# 1GB_DDR3L_Modules.net
KiCad netlist of a schematic drawn in Altium Designer
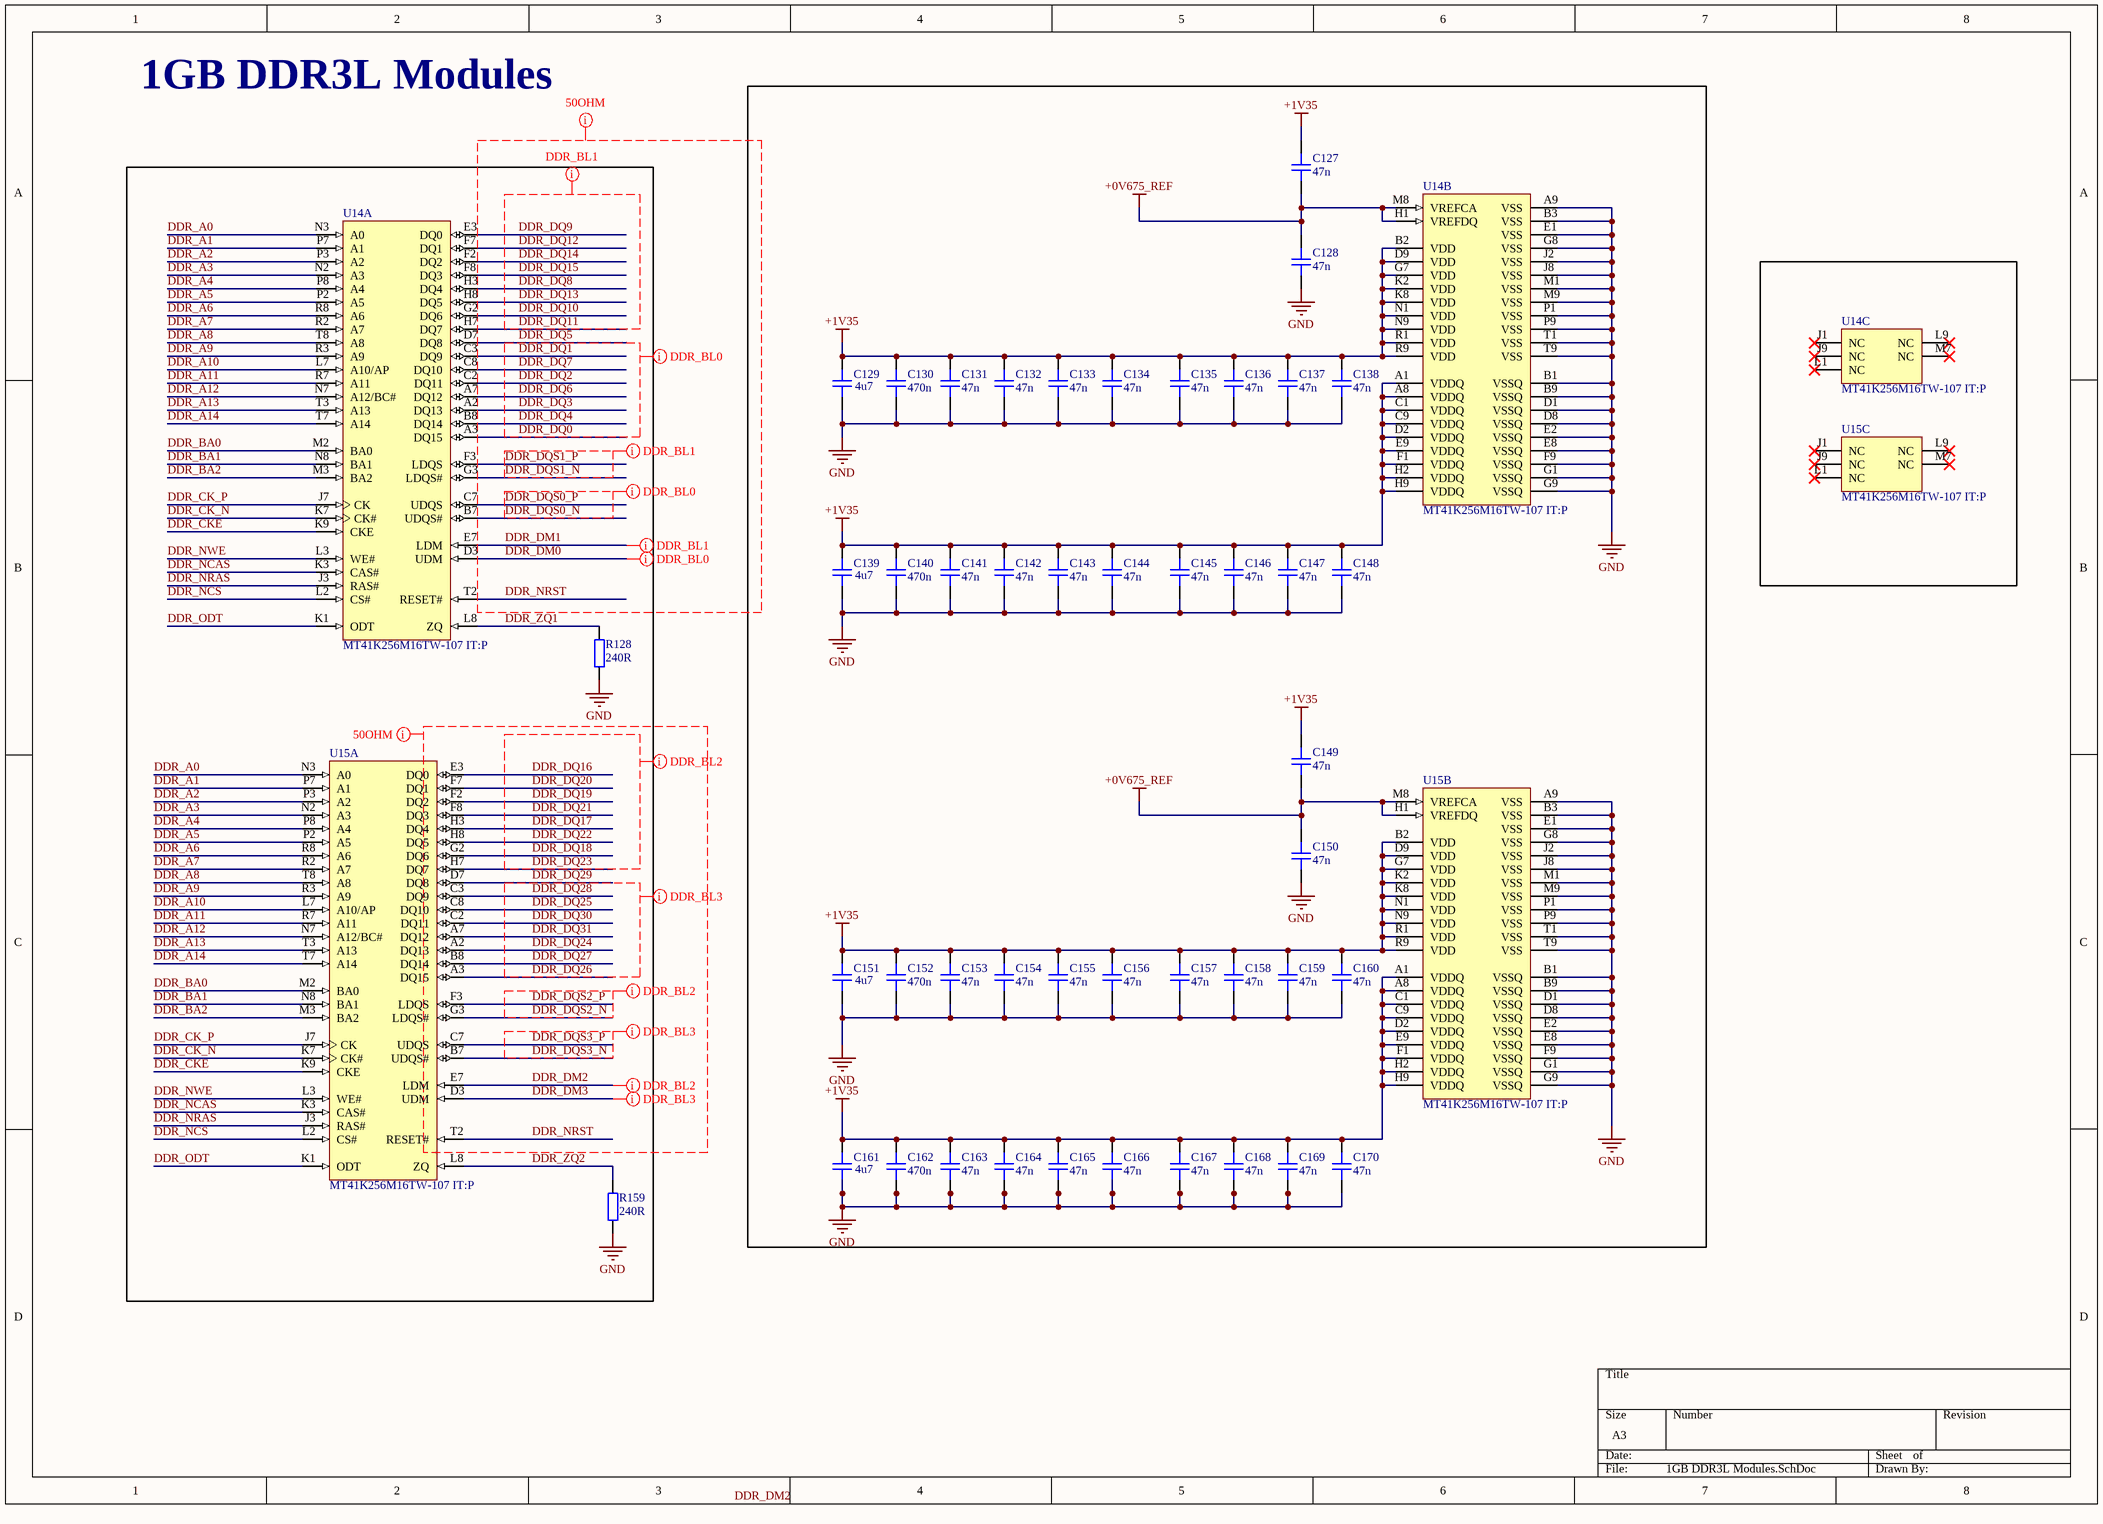
[diagram p0: 1GB DDR3L Modules.SchDoc]

(export (version "E")
  (design (tool "Eeschema 10.0.6"))
  (components
    (comp (ref "C127")
      (value "47n")
      (footprint "CAP_0201")
      (description "Capacitor SMD 0201")
      (fields (field (name "Comment") "C0201"))
      (libsource (lib "Schematic-Lib-PhilsLab") (part "CAP_0201"))
    )
    (comp (ref "C128")
      (value "47n")
      (footprint "CAP_0201")
      (description "Capacitor SMD 0201")
      (fields (field (name "Comment") "C0201"))
      (libsource (lib "Schematic-Lib-PhilsLab") (part "CAP_0201"))
    )
    (comp (ref "C129")
      (value "4u7")
      (footprint "CAP_0402")
      (description "Capacitor SMD 0402")
      (fields (field (name "Comment") "C0402"))
      (libsource (lib "Schematic-Lib-PhilsLab") (part "CAP_0402"))
    )
    (comp (ref "C130")
      (value "470n")
      (footprint "CAP_0201")
      (description "Capacitor SMD 0201")
      (fields (field (name "Comment") "C0201"))
      (libsource (lib "Schematic-Lib-PhilsLab") (part "CAP_0201"))
    )
    (comp (ref "C131")
      (value "47n")
      (footprint "CAP_0201")
      (description "Capacitor SMD 0201")
      (fields (field (name "Comment") "C0201"))
      (libsource (lib "Schematic-Lib-PhilsLab") (part "CAP_0201"))
    )
    (comp (ref "C132")
      (value "47n")
      (footprint "CAP_0201")
      (description "Capacitor SMD 0201")
      (fields (field (name "Comment") "C0201"))
      (libsource (lib "Schematic-Lib-PhilsLab") (part "CAP_0201"))
    )
    (comp (ref "C133")
      (value "47n")
      (footprint "CAP_0201")
      (description "Capacitor SMD 0201")
      (fields (field (name "Comment") "C0201"))
      (libsource (lib "Schematic-Lib-PhilsLab") (part "CAP_0201"))
    )
    (comp (ref "C134")
      (value "47n")
      (footprint "CAP_0201")
      (description "Capacitor SMD 0201")
      (fields (field (name "Comment") "C0201"))
      (libsource (lib "Schematic-Lib-PhilsLab") (part "CAP_0201"))
    )
    (comp (ref "C135")
      (value "47n")
      (footprint "CAP_0201")
      (description "Capacitor SMD 0201")
      (fields (field (name "Comment") "C0201"))
      (libsource (lib "Schematic-Lib-PhilsLab") (part "CAP_0201"))
    )
    (comp (ref "C136")
      (value "47n")
      (footprint "CAP_0201")
      (description "Capacitor SMD 0201")
      (fields (field (name "Comment") "C0201"))
      (libsource (lib "Schematic-Lib-PhilsLab") (part "CAP_0201"))
    )
    (comp (ref "C137")
      (value "47n")
      (footprint "CAP_0201")
      (description "Capacitor SMD 0201")
      (fields (field (name "Comment") "C0201"))
      (libsource (lib "Schematic-Lib-PhilsLab") (part "CAP_0201"))
    )
    (comp (ref "C138")
      (value "47n")
      (footprint "CAP_0201")
      (description "Capacitor SMD 0201")
      (fields (field (name "Comment") "C0201"))
      (libsource (lib "Schematic-Lib-PhilsLab") (part "CAP_0201"))
    )
    (comp (ref "C139")
      (value "4u7")
      (footprint "CAP_0402")
      (description "Capacitor SMD 0402")
      (fields (field (name "Comment") "C0402"))
      (libsource (lib "Schematic-Lib-PhilsLab") (part "CAP_0402"))
    )
    (comp (ref "C140")
      (value "470n")
      (footprint "CAP_0201")
      (description "Capacitor SMD 0201")
      (fields (field (name "Comment") "C0201"))
      (libsource (lib "Schematic-Lib-PhilsLab") (part "CAP_0201"))
    )
    (comp (ref "C141")
      (value "47n")
      (footprint "CAP_0201")
      (description "Capacitor SMD 0201")
      (fields (field (name "Comment") "C0201"))
      (libsource (lib "Schematic-Lib-PhilsLab") (part "CAP_0201"))
    )
    (comp (ref "C142")
      (value "47n")
      (footprint "CAP_0201")
      (description "Capacitor SMD 0201")
      (fields (field (name "Comment") "C0201"))
      (libsource (lib "Schematic-Lib-PhilsLab") (part "CAP_0201"))
    )
    (comp (ref "C143")
      (value "47n")
      (footprint "CAP_0201")
      (description "Capacitor SMD 0201")
      (fields (field (name "Comment") "C0201"))
      (libsource (lib "Schematic-Lib-PhilsLab") (part "CAP_0201"))
    )
    (comp (ref "C144")
      (value "47n")
      (footprint "CAP_0201")
      (description "Capacitor SMD 0201")
      (fields (field (name "Comment") "C0201"))
      (libsource (lib "Schematic-Lib-PhilsLab") (part "CAP_0201"))
    )
    (comp (ref "C145")
      (value "47n")
      (footprint "CAP_0201")
      (description "Capacitor SMD 0201")
      (fields (field (name "Comment") "C0201"))
      (libsource (lib "Schematic-Lib-PhilsLab") (part "CAP_0201"))
    )
    (comp (ref "C146")
      (value "47n")
      (footprint "CAP_0201")
      (description "Capacitor SMD 0201")
      (fields (field (name "Comment") "C0201"))
      (libsource (lib "Schematic-Lib-PhilsLab") (part "CAP_0201"))
    )
    (comp (ref "C147")
      (value "47n")
      (footprint "CAP_0201")
      (description "Capacitor SMD 0201")
      (fields (field (name "Comment") "C0201"))
      (libsource (lib "Schematic-Lib-PhilsLab") (part "CAP_0201"))
    )
    (comp (ref "C148")
      (value "47n")
      (footprint "CAP_0201")
      (description "Capacitor SMD 0201")
      (fields (field (name "Comment") "C0201"))
      (libsource (lib "Schematic-Lib-PhilsLab") (part "CAP_0201"))
    )
    (comp (ref "C149")
      (value "47n")
      (footprint "CAP_0201")
      (description "Capacitor SMD 0201")
      (fields (field (name "Comment") "C0201"))
      (libsource (lib "Schematic-Lib-PhilsLab") (part "CAP_0201"))
    )
    (comp (ref "C150")
      (value "47n")
      (footprint "CAP_0201")
      (description "Capacitor SMD 0201")
      (fields (field (name "Comment") "C0201"))
      (libsource (lib "Schematic-Lib-PhilsLab") (part "CAP_0201"))
    )
    (comp (ref "C151")
      (value "4u7")
      (footprint "CAP_0402")
      (description "Capacitor SMD 0402")
      (fields (field (name "Comment") "C0402"))
      (libsource (lib "Schematic-Lib-PhilsLab") (part "CAP_0402"))
    )
    (comp (ref "C152")
      (value "470n")
      (footprint "CAP_0201")
      (description "Capacitor SMD 0201")
      (fields (field (name "Comment") "C0201"))
      (libsource (lib "Schematic-Lib-PhilsLab") (part "CAP_0201"))
    )
    (comp (ref "C153")
      (value "47n")
      (footprint "CAP_0201")
      (description "Capacitor SMD 0201")
      (fields (field (name "Comment") "C0201"))
      (libsource (lib "Schematic-Lib-PhilsLab") (part "CAP_0201"))
    )
    (comp (ref "C154")
      (value "47n")
      (footprint "CAP_0201")
      (description "Capacitor SMD 0201")
      (fields (field (name "Comment") "C0201"))
      (libsource (lib "Schematic-Lib-PhilsLab") (part "CAP_0201"))
    )
    (comp (ref "C155")
      (value "47n")
      (footprint "CAP_0201")
      (description "Capacitor SMD 0201")
      (fields (field (name "Comment") "C0201"))
      (libsource (lib "Schematic-Lib-PhilsLab") (part "CAP_0201"))
    )
    (comp (ref "C156")
      (value "47n")
      (footprint "CAP_0201")
      (description "Capacitor SMD 0201")
      (fields (field (name "Comment") "C0201"))
      (libsource (lib "Schematic-Lib-PhilsLab") (part "CAP_0201"))
    )
    (comp (ref "C157")
      (value "47n")
      (footprint "CAP_0201")
      (description "Capacitor SMD 0201")
      (fields (field (name "Comment") "C0201"))
      (libsource (lib "Schematic-Lib-PhilsLab") (part "CAP_0201"))
    )
    (comp (ref "C158")
      (value "47n")
      (footprint "CAP_0201")
      (description "Capacitor SMD 0201")
      (fields (field (name "Comment") "C0201"))
      (libsource (lib "Schematic-Lib-PhilsLab") (part "CAP_0201"))
    )
    (comp (ref "C159")
      (value "47n")
      (footprint "CAP_0201")
      (description "Capacitor SMD 0201")
      (fields (field (name "Comment") "C0201"))
      (libsource (lib "Schematic-Lib-PhilsLab") (part "CAP_0201"))
    )
    (comp (ref "C160")
      (value "47n")
      (footprint "CAP_0201")
      (description "Capacitor SMD 0201")
      (fields (field (name "Comment") "C0201"))
      (libsource (lib "Schematic-Lib-PhilsLab") (part "CAP_0201"))
    )
    (comp (ref "C161")
      (value "4u7")
      (footprint "CAP_0402")
      (description "Capacitor SMD 0402")
      (fields (field (name "Comment") "C0402"))
      (libsource (lib "Schematic-Lib-PhilsLab") (part "CAP_0402"))
    )
    (comp (ref "C162")
      (value "470n")
      (footprint "CAP_0201")
      (description "Capacitor SMD 0201")
      (fields (field (name "Comment") "C0201"))
      (libsource (lib "Schematic-Lib-PhilsLab") (part "CAP_0201"))
    )
    (comp (ref "C163")
      (value "47n")
      (footprint "CAP_0201")
      (description "Capacitor SMD 0201")
      (fields (field (name "Comment") "C0201"))
      (libsource (lib "Schematic-Lib-PhilsLab") (part "CAP_0201"))
    )
    (comp (ref "C164")
      (value "47n")
      (footprint "CAP_0201")
      (description "Capacitor SMD 0201")
      (fields (field (name "Comment") "C0201"))
      (libsource (lib "Schematic-Lib-PhilsLab") (part "CAP_0201"))
    )
    (comp (ref "C165")
      (value "47n")
      (footprint "CAP_0201")
      (description "Capacitor SMD 0201")
      (fields (field (name "Comment") "C0201"))
      (libsource (lib "Schematic-Lib-PhilsLab") (part "CAP_0201"))
    )
    (comp (ref "C166")
      (value "47n")
      (footprint "CAP_0201")
      (description "Capacitor SMD 0201")
      (fields (field (name "Comment") "C0201"))
      (libsource (lib "Schematic-Lib-PhilsLab") (part "CAP_0201"))
    )
    (comp (ref "C167")
      (value "47n")
      (footprint "CAP_0201")
      (description "Capacitor SMD 0201")
      (fields (field (name "Comment") "C0201"))
      (libsource (lib "Schematic-Lib-PhilsLab") (part "CAP_0201"))
    )
    (comp (ref "C168")
      (value "47n")
      (footprint "CAP_0201")
      (description "Capacitor SMD 0201")
      (fields (field (name "Comment") "C0201"))
      (libsource (lib "Schematic-Lib-PhilsLab") (part "CAP_0201"))
    )
    (comp (ref "C169")
      (value "47n")
      (footprint "CAP_0201")
      (description "Capacitor SMD 0201")
      (fields (field (name "Comment") "C0201"))
      (libsource (lib "Schematic-Lib-PhilsLab") (part "CAP_0201"))
    )
    (comp (ref "C170")
      (value "47n")
      (footprint "CAP_0201")
      (description "Capacitor SMD 0201")
      (fields (field (name "Comment") "C0201"))
      (libsource (lib "Schematic-Lib-PhilsLab") (part "CAP_0201"))
    )
    (comp (ref "R128")
      (value "240R")
      (footprint "RES_0402")
      (description "Resistor SMD 0402")
      (fields (field (name "Comment") "R0402"))
      (libsource (lib "Schematic-Lib-PhilsLab") (part "RES_0402"))
    )
    (comp (ref "R159")
      (value "240R")
      (footprint "RES_0402")
      (description "Resistor SMD 0402")
      (fields (field (name "Comment") "R0402"))
      (libsource (lib "Schematic-Lib-PhilsLab") (part "RES_0402"))
    )
    (comp (ref "U14")
      (value "MT41K256M16TW-107 IT:P")
      (footprint "MICT-TW-96")
      (description "Automotive DDR3L SDRAM, 4 GB, 933 MHz, 1.283 to 1.45 V, -40 to 95 degC, 96-Pin TFBGA, RoHS, Tray")
      (fields (field (name "MANUFACTURER") "Micron"))
      (libsource (lib "Altium Content Vault") (part "MICT-MT41K256M16-TW-96"))
    )
    (comp (ref "U15")
      (value "MT41K256M16TW-107 IT:P")
      (footprint "MICT-TW-96")
      (description "Automotive DDR3L SDRAM, 4 GB, 933 MHz, 1.283 to 1.45 V, -40 to 95 degC, 96-Pin TFBGA, RoHS, Tray")
      (fields (field (name "MANUFACTURER") "Micron"))
      (libsource (lib "Altium Content Vault") (part "MICT-MT41K256M16-TW-96"))
    )
  )
  (nets
    (net (code "1") (name "+0V675_REF") (class "Default")
      (node (ref "C127") (pin "1") (pinfunction "1_1") (pintype "passive"))
      (node (ref "C128") (pin "2") (pinfunction "2_2") (pintype "passive"))
      (node (ref "C149") (pin "1") (pinfunction "1_1") (pintype "passive"))
      (node (ref "C150") (pin "2") (pinfunction "2_2") (pintype "passive"))
      (node (ref "U14") (pin "H1") (pinfunction "VREFDQ_H1") (pintype "input"))
      (node (ref "U14") (pin "M8") (pinfunction "VREFCA_M8") (pintype "input"))
      (node (ref "U15") (pin "H1") (pinfunction "VREFDQ_H1") (pintype "input"))
      (node (ref "U15") (pin "M8") (pinfunction "VREFCA_M8") (pintype "input"))
    )
    (net (code "2") (name "+1V35") (class "Default")
      (node (ref "C127") (pin "2") (pinfunction "2_2") (pintype "passive"))
      (node (ref "C129") (pin "2") (pinfunction "2_2") (pintype "passive"))
      (node (ref "C130") (pin "2") (pinfunction "2_2") (pintype "passive"))
      (node (ref "C131") (pin "2") (pinfunction "2_2") (pintype "passive"))
      (node (ref "C132") (pin "2") (pinfunction "2_2") (pintype "passive"))
      (node (ref "C133") (pin "2") (pinfunction "2_2") (pintype "passive"))
      (node (ref "C134") (pin "2") (pinfunction "2_2") (pintype "passive"))
      (node (ref "C135") (pin "2") (pinfunction "2_2") (pintype "passive"))
      (node (ref "C136") (pin "2") (pinfunction "2_2") (pintype "passive"))
      (node (ref "C137") (pin "2") (pinfunction "2_2") (pintype "passive"))
      (node (ref "C138") (pin "2") (pinfunction "2_2") (pintype "passive"))
      (node (ref "C139") (pin "2") (pinfunction "2_2") (pintype "passive"))
      (node (ref "C140") (pin "2") (pinfunction "2_2") (pintype "passive"))
      (node (ref "C141") (pin "2") (pinfunction "2_2") (pintype "passive"))
      (node (ref "C142") (pin "2") (pinfunction "2_2") (pintype "passive"))
      (node (ref "C143") (pin "2") (pinfunction "2_2") (pintype "passive"))
      (node (ref "C144") (pin "2") (pinfunction "2_2") (pintype "passive"))
      (node (ref "C145") (pin "2") (pinfunction "2_2") (pintype "passive"))
      (node (ref "C146") (pin "2") (pinfunction "2_2") (pintype "passive"))
      (node (ref "C147") (pin "2") (pinfunction "2_2") (pintype "passive"))
      (node (ref "C148") (pin "2") (pinfunction "2_2") (pintype "passive"))
      (node (ref "C149") (pin "2") (pinfunction "2_2") (pintype "passive"))
      (node (ref "C151") (pin "2") (pinfunction "2_2") (pintype "passive"))
      (node (ref "C152") (pin "2") (pinfunction "2_2") (pintype "passive"))
      (node (ref "C153") (pin "2") (pinfunction "2_2") (pintype "passive"))
      (node (ref "C154") (pin "2") (pinfunction "2_2") (pintype "passive"))
      (node (ref "C155") (pin "2") (pinfunction "2_2") (pintype "passive"))
      (node (ref "C156") (pin "2") (pinfunction "2_2") (pintype "passive"))
      (node (ref "C157") (pin "2") (pinfunction "2_2") (pintype "passive"))
      (node (ref "C158") (pin "2") (pinfunction "2_2") (pintype "passive"))
      (node (ref "C159") (pin "2") (pinfunction "2_2") (pintype "passive"))
      (node (ref "C160") (pin "2") (pinfunction "2_2") (pintype "passive"))
      (node (ref "C161") (pin "2") (pinfunction "2_2") (pintype "passive"))
      (node (ref "C162") (pin "2") (pinfunction "2_2") (pintype "passive"))
      (node (ref "C163") (pin "2") (pinfunction "2_2") (pintype "passive"))
      (node (ref "C164") (pin "2") (pinfunction "2_2") (pintype "passive"))
      (node (ref "C165") (pin "2") (pinfunction "2_2") (pintype "passive"))
      (node (ref "C166") (pin "2") (pinfunction "2_2") (pintype "passive"))
      (node (ref "C167") (pin "2") (pinfunction "2_2") (pintype "passive"))
      (node (ref "C168") (pin "2") (pinfunction "2_2") (pintype "passive"))
      (node (ref "C169") (pin "2") (pinfunction "2_2") (pintype "passive"))
      (node (ref "C170") (pin "2") (pinfunction "2_2") (pintype "passive"))
      (node (ref "U14") (pin "A1") (pinfunction "VDDQ_A1") (pintype "power_in"))
      (node (ref "U14") (pin "A8") (pinfunction "VDDQ_A8") (pintype "power_in"))
      (node (ref "U14") (pin "B2") (pinfunction "VDD_B2") (pintype "power_in"))
      (node (ref "U14") (pin "C1") (pinfunction "VDDQ_C1") (pintype "power_in"))
      (node (ref "U14") (pin "C9") (pinfunction "VDDQ_C9") (pintype "power_in"))
      (node (ref "U14") (pin "D2") (pinfunction "VDDQ_D2") (pintype "power_in"))
      (node (ref "U14") (pin "D9") (pinfunction "VDD_D9") (pintype "power_in"))
      (node (ref "U14") (pin "E9") (pinfunction "VDDQ_E9") (pintype "power_in"))
      (node (ref "U14") (pin "F1") (pinfunction "VDDQ_F1") (pintype "power_in"))
      (node (ref "U14") (pin "G7") (pinfunction "VDD_G7") (pintype "power_in"))
      (node (ref "U14") (pin "H2") (pinfunction "VDDQ_H2") (pintype "power_in"))
      (node (ref "U14") (pin "H9") (pinfunction "VDDQ_H9") (pintype "power_in"))
      (node (ref "U14") (pin "K2") (pinfunction "VDD_K2") (pintype "power_in"))
      (node (ref "U14") (pin "K8") (pinfunction "VDD_K8") (pintype "power_in"))
      (node (ref "U14") (pin "N1") (pinfunction "VDD_N1") (pintype "power_in"))
      (node (ref "U14") (pin "N9") (pinfunction "VDD_N9") (pintype "power_in"))
      (node (ref "U14") (pin "R1") (pinfunction "VDD_R1") (pintype "power_in"))
      (node (ref "U14") (pin "R9") (pinfunction "VDD_R9") (pintype "power_in"))
      (node (ref "U15") (pin "A1") (pinfunction "VDDQ_A1") (pintype "power_in"))
      (node (ref "U15") (pin "A8") (pinfunction "VDDQ_A8") (pintype "power_in"))
      (node (ref "U15") (pin "B2") (pinfunction "VDD_B2") (pintype "power_in"))
      (node (ref "U15") (pin "C1") (pinfunction "VDDQ_C1") (pintype "power_in"))
      (node (ref "U15") (pin "C9") (pinfunction "VDDQ_C9") (pintype "power_in"))
      (node (ref "U15") (pin "D2") (pinfunction "VDDQ_D2") (pintype "power_in"))
      (node (ref "U15") (pin "D9") (pinfunction "VDD_D9") (pintype "power_in"))
      (node (ref "U15") (pin "E9") (pinfunction "VDDQ_E9") (pintype "power_in"))
      (node (ref "U15") (pin "F1") (pinfunction "VDDQ_F1") (pintype "power_in"))
      (node (ref "U15") (pin "G7") (pinfunction "VDD_G7") (pintype "power_in"))
      (node (ref "U15") (pin "H2") (pinfunction "VDDQ_H2") (pintype "power_in"))
      (node (ref "U15") (pin "H9") (pinfunction "VDDQ_H9") (pintype "power_in"))
      (node (ref "U15") (pin "K2") (pinfunction "VDD_K2") (pintype "power_in"))
      (node (ref "U15") (pin "K8") (pinfunction "VDD_K8") (pintype "power_in"))
      (node (ref "U15") (pin "N1") (pinfunction "VDD_N1") (pintype "power_in"))
      (node (ref "U15") (pin "N9") (pinfunction "VDD_N9") (pintype "power_in"))
      (node (ref "U15") (pin "R1") (pinfunction "VDD_R1") (pintype "power_in"))
      (node (ref "U15") (pin "R9") (pinfunction "VDD_R9") (pintype "power_in"))
    )
    (net (code "3") (name "/DDR_A0") (class "Default")
      (node (ref "U14") (pin "N3") (pinfunction "A0_N3") (pintype "input"))
      (node (ref "U15") (pin "N3") (pinfunction "A0_N3") (pintype "input"))
    )
    (net (code "4") (name "/DDR_A1") (class "Default")
      (node (ref "U14") (pin "P7") (pinfunction "A1_P7") (pintype "input"))
      (node (ref "U15") (pin "P7") (pinfunction "A1_P7") (pintype "input"))
    )
    (net (code "5") (name "/DDR_A2") (class "Default")
      (node (ref "U14") (pin "P3") (pinfunction "A2_P3") (pintype "input"))
      (node (ref "U15") (pin "P3") (pinfunction "A2_P3") (pintype "input"))
    )
    (net (code "6") (name "/DDR_A3") (class "Default")
      (node (ref "U14") (pin "N2") (pinfunction "A3_N2") (pintype "input"))
      (node (ref "U15") (pin "N2") (pinfunction "A3_N2") (pintype "input"))
    )
    (net (code "7") (name "/DDR_A4") (class "Default")
      (node (ref "U14") (pin "P8") (pinfunction "A4_P8") (pintype "input"))
      (node (ref "U15") (pin "P8") (pinfunction "A4_P8") (pintype "input"))
    )
    (net (code "8") (name "/DDR_A5") (class "Default")
      (node (ref "U14") (pin "P2") (pinfunction "A5_P2") (pintype "input"))
      (node (ref "U15") (pin "P2") (pinfunction "A5_P2") (pintype "input"))
    )
    (net (code "9") (name "/DDR_A6") (class "Default")
      (node (ref "U14") (pin "R8") (pinfunction "A6_R8") (pintype "input"))
      (node (ref "U15") (pin "R8") (pinfunction "A6_R8") (pintype "input"))
    )
    (net (code "10") (name "/DDR_A7") (class "Default")
      (node (ref "U14") (pin "R2") (pinfunction "A7_R2") (pintype "input"))
      (node (ref "U15") (pin "R2") (pinfunction "A7_R2") (pintype "input"))
    )
    (net (code "11") (name "/DDR_A8") (class "Default")
      (node (ref "U14") (pin "T8") (pinfunction "A8_T8") (pintype "input"))
      (node (ref "U15") (pin "T8") (pinfunction "A8_T8") (pintype "input"))
    )
    (net (code "12") (name "/DDR_A9") (class "Default")
      (node (ref "U14") (pin "R3") (pinfunction "A9_R3") (pintype "input"))
      (node (ref "U15") (pin "R3") (pinfunction "A9_R3") (pintype "input"))
    )
    (net (code "13") (name "/DDR_A10") (class "Default")
      (node (ref "U14") (pin "L7") (pinfunction "A10/AP_L7") (pintype "input"))
      (node (ref "U15") (pin "L7") (pinfunction "A10/AP_L7") (pintype "input"))
    )
    (net (code "14") (name "/DDR_A11") (class "Default")
      (node (ref "U14") (pin "R7") (pinfunction "A11_R7") (pintype "input"))
      (node (ref "U15") (pin "R7") (pinfunction "A11_R7") (pintype "input"))
    )
    (net (code "15") (name "/DDR_A12") (class "Default")
      (node (ref "U14") (pin "N7") (pinfunction "A12/BC#_N7") (pintype "input"))
      (node (ref "U15") (pin "N7") (pinfunction "A12/BC#_N7") (pintype "input"))
    )
    (net (code "16") (name "/DDR_A13") (class "Default")
      (node (ref "U14") (pin "T3") (pinfunction "A13_T3") (pintype "input"))
      (node (ref "U15") (pin "T3") (pinfunction "A13_T3") (pintype "input"))
    )
    (net (code "17") (name "/DDR_A14") (class "Default")
      (node (ref "U14") (pin "T7") (pinfunction "A14_T7") (pintype "input"))
      (node (ref "U15") (pin "T7") (pinfunction "A14_T7") (pintype "input"))
    )
    (net (code "18") (name "/DDR_BA0") (class "Default")
      (node (ref "U14") (pin "M2") (pinfunction "BA0_M2") (pintype "input"))
      (node (ref "U15") (pin "M2") (pinfunction "BA0_M2") (pintype "input"))
    )
    (net (code "19") (name "/DDR_BA1") (class "Default")
      (node (ref "U14") (pin "N8") (pinfunction "BA1_N8") (pintype "input"))
      (node (ref "U15") (pin "N8") (pinfunction "BA1_N8") (pintype "input"))
    )
    (net (code "20") (name "/DDR_BA2") (class "Default")
      (node (ref "U14") (pin "M3") (pinfunction "BA2_M3") (pintype "input"))
      (node (ref "U15") (pin "M3") (pinfunction "BA2_M3") (pintype "input"))
    )
    (net (code "21") (name "/DDR_CKE") (class "Default")
      (node (ref "U14") (pin "K9") (pinfunction "CKE_K9") (pintype "input"))
      (node (ref "U15") (pin "K9") (pinfunction "CKE_K9") (pintype "input"))
    )
    (net (code "22") (name "/DDR_CK_N") (class "Default")
      (node (ref "U14") (pin "K7") (pinfunction "CK#_K7") (pintype "input"))
      (node (ref "U15") (pin "K7") (pinfunction "CK#_K7") (pintype "input"))
    )
    (net (code "23") (name "/DDR_CK_P") (class "Default")
      (node (ref "U14") (pin "J7") (pinfunction "CK_J7") (pintype "input"))
      (node (ref "U15") (pin "J7") (pinfunction "CK_J7") (pintype "input"))
    )
    (net (code "24") (name "/DDR_DM0") (class "Default")
      (node (ref "U14") (pin "D3") (pinfunction "UDM_D3") (pintype "input"))
    )
    (net (code "25") (name "/DDR_DM1") (class "Default")
      (node (ref "U14") (pin "E7") (pinfunction "LDM_E7") (pintype "input"))
    )
    (net (code "26") (name "/DDR_DM2") (class "Default")
      (node (ref "U15") (pin "E7") (pinfunction "LDM_E7") (pintype "input"))
    )
    (net (code "27") (name "/DDR_DM3") (class "Default")
      (node (ref "U15") (pin "D3") (pinfunction "UDM_D3") (pintype "input"))
    )
    (net (code "28") (name "/DDR_DQ0") (class "Default")
      (node (ref "U14") (pin "A3") (pinfunction "DQ15_A3") (pintype "bidirectional"))
    )
    (net (code "29") (name "/DDR_DQ1") (class "Default")
      (node (ref "U14") (pin "C3") (pinfunction "DQ9_C3") (pintype "bidirectional"))
    )
    (net (code "30") (name "/DDR_DQ2") (class "Default")
      (node (ref "U14") (pin "C2") (pinfunction "DQ11_C2") (pintype "bidirectional"))
    )
    (net (code "31") (name "/DDR_DQ3") (class "Default")
      (node (ref "U14") (pin "A2") (pinfunction "DQ13_A2") (pintype "bidirectional"))
    )
    (net (code "32") (name "/DDR_DQ4") (class "Default")
      (node (ref "U14") (pin "B8") (pinfunction "DQ14_B8") (pintype "bidirectional"))
    )
    (net (code "33") (name "/DDR_DQ5") (class "Default")
      (node (ref "U14") (pin "D7") (pinfunction "DQ8_D7") (pintype "bidirectional"))
    )
    (net (code "34") (name "/DDR_DQ6") (class "Default")
      (node (ref "U14") (pin "A7") (pinfunction "DQ12_A7") (pintype "bidirectional"))
    )
    (net (code "35") (name "/DDR_DQ7") (class "Default")
      (node (ref "U14") (pin "C8") (pinfunction "DQ10_C8") (pintype "bidirectional"))
    )
    (net (code "36") (name "/DDR_DQ8") (class "Default")
      (node (ref "U14") (pin "H3") (pinfunction "DQ4_H3") (pintype "bidirectional"))
    )
    (net (code "37") (name "/DDR_DQ9") (class "Default")
      (node (ref "U14") (pin "E3") (pinfunction "DQ0_E3") (pintype "bidirectional"))
    )
    (net (code "38") (name "/DDR_DQ10") (class "Default")
      (node (ref "U14") (pin "G2") (pinfunction "DQ6_G2") (pintype "bidirectional"))
    )
    (net (code "39") (name "/DDR_DQ11") (class "Default")
      (node (ref "U14") (pin "H7") (pinfunction "DQ7_H7") (pintype "bidirectional"))
    )
    (net (code "40") (name "/DDR_DQ12") (class "Default")
      (node (ref "U14") (pin "F7") (pinfunction "DQ1_F7") (pintype "bidirectional"))
    )
    (net (code "41") (name "/DDR_DQ13") (class "Default")
      (node (ref "U14") (pin "H8") (pinfunction "DQ5_H8") (pintype "bidirectional"))
    )
    (net (code "42") (name "/DDR_DQ14") (class "Default")
      (node (ref "U14") (pin "F2") (pinfunction "DQ2_F2") (pintype "bidirectional"))
    )
    (net (code "43") (name "/DDR_DQ15") (class "Default")
      (node (ref "U14") (pin "F8") (pinfunction "DQ3_F8") (pintype "bidirectional"))
    )
    (net (code "44") (name "/DDR_DQ16") (class "Default")
      (node (ref "U15") (pin "E3") (pinfunction "DQ0_E3") (pintype "bidirectional"))
    )
    (net (code "45") (name "/DDR_DQ17") (class "Default")
      (node (ref "U15") (pin "H3") (pinfunction "DQ4_H3") (pintype "bidirectional"))
    )
    (net (code "46") (name "/DDR_DQ18") (class "Default")
      (node (ref "U15") (pin "G2") (pinfunction "DQ6_G2") (pintype "bidirectional"))
    )
    (net (code "47") (name "/DDR_DQ19") (class "Default")
      (node (ref "U15") (pin "F2") (pinfunction "DQ2_F2") (pintype "bidirectional"))
    )
    (net (code "48") (name "/DDR_DQ20") (class "Default")
      (node (ref "U15") (pin "F7") (pinfunction "DQ1_F7") (pintype "bidirectional"))
    )
    (net (code "49") (name "/DDR_DQ21") (class "Default")
      (node (ref "U15") (pin "F8") (pinfunction "DQ3_F8") (pintype "bidirectional"))
    )
    (net (code "50") (name "/DDR_DQ22") (class "Default")
      (node (ref "U15") (pin "H8") (pinfunction "DQ5_H8") (pintype "bidirectional"))
    )
    (net (code "51") (name "/DDR_DQ23") (class "Default")
      (node (ref "U15") (pin "H7") (pinfunction "DQ7_H7") (pintype "bidirectional"))
    )
    (net (code "52") (name "/DDR_DQ24") (class "Default")
      (node (ref "U15") (pin "A2") (pinfunction "DQ13_A2") (pintype "bidirectional"))
    )
    (net (code "53") (name "/DDR_DQ25") (class "Default")
      (node (ref "U15") (pin "C8") (pinfunction "DQ10_C8") (pintype "bidirectional"))
    )
    (net (code "54") (name "/DDR_DQ26") (class "Default")
      (node (ref "U15") (pin "A3") (pinfunction "DQ15_A3") (pintype "bidirectional"))
    )
    (net (code "55") (name "/DDR_DQ27") (class "Default")
      (node (ref "U15") (pin "B8") (pinfunction "DQ14_B8") (pintype "bidirectional"))
    )
    (net (code "56") (name "/DDR_DQ28") (class "Default")
      (node (ref "U15") (pin "C3") (pinfunction "DQ9_C3") (pintype "bidirectional"))
    )
    (net (code "57") (name "/DDR_DQ29") (class "Default")
      (node (ref "U15") (pin "D7") (pinfunction "DQ8_D7") (pintype "bidirectional"))
    )
    (net (code "58") (name "/DDR_DQ30") (class "Default")
      (node (ref "U15") (pin "C2") (pinfunction "DQ11_C2") (pintype "bidirectional"))
    )
    (net (code "59") (name "/DDR_DQ31") (class "Default")
      (node (ref "U15") (pin "A7") (pinfunction "DQ12_A7") (pintype "bidirectional"))
    )
    (net (code "60") (name "/DDR_DQS0_N") (class "Default")
      (node (ref "U14") (pin "B7") (pinfunction "UDQS#_B7") (pintype "bidirectional"))
    )
    (net (code "61") (name "/DDR_DQS0_P") (class "Default")
      (node (ref "U14") (pin "C7") (pinfunction "UDQS_C7") (pintype "bidirectional"))
    )
    (net (code "62") (name "/DDR_DQS1_N") (class "Default")
      (node (ref "U14") (pin "G3") (pinfunction "LDQS#_G3") (pintype "bidirectional"))
    )
    (net (code "63") (name "/DDR_DQS1_P") (class "Default")
      (node (ref "U14") (pin "F3") (pinfunction "LDQS_F3") (pintype "bidirectional"))
    )
    (net (code "64") (name "/DDR_DQS2_N") (class "Default")
      (node (ref "U15") (pin "G3") (pinfunction "LDQS#_G3") (pintype "bidirectional"))
    )
    (net (code "65") (name "/DDR_DQS2_P") (class "Default")
      (node (ref "U15") (pin "F3") (pinfunction "LDQS_F3") (pintype "bidirectional"))
    )
    (net (code "66") (name "/DDR_DQS3_N") (class "Default")
      (node (ref "U15") (pin "B7") (pinfunction "UDQS#_B7") (pintype "bidirectional"))
    )
    (net (code "67") (name "/DDR_DQS3_P") (class "Default")
      (node (ref "U15") (pin "C7") (pinfunction "UDQS_C7") (pintype "bidirectional"))
    )
    (net (code "68") (name "/DDR_NCAS") (class "Default")
      (node (ref "U14") (pin "K3") (pinfunction "CAS#_K3") (pintype "input"))
      (node (ref "U15") (pin "K3") (pinfunction "CAS#_K3") (pintype "input"))
    )
    (net (code "69") (name "/DDR_NCS") (class "Default")
      (node (ref "U14") (pin "L2") (pinfunction "CS#_L2") (pintype "input"))
      (node (ref "U15") (pin "L2") (pinfunction "CS#_L2") (pintype "input"))
    )
    (net (code "70") (name "/DDR_NRAS") (class "Default")
      (node (ref "U14") (pin "J3") (pinfunction "RAS#_J3") (pintype "input"))
      (node (ref "U15") (pin "J3") (pinfunction "RAS#_J3") (pintype "input"))
    )
    (net (code "71") (name "/DDR_NRST") (class "Default")
      (node (ref "U14") (pin "T2") (pinfunction "RESET#_T2") (pintype "input"))
      (node (ref "U15") (pin "T2") (pinfunction "RESET#_T2") (pintype "input"))
    )
    (net (code "72") (name "/DDR_NWE") (class "Default")
      (node (ref "U14") (pin "L3") (pinfunction "WE#_L3") (pintype "input"))
      (node (ref "U15") (pin "L3") (pinfunction "WE#_L3") (pintype "input"))
    )
    (net (code "73") (name "/DDR_ODT") (class "Default")
      (node (ref "U14") (pin "K1") (pinfunction "ODT_K1") (pintype "input"))
      (node (ref "U15") (pin "K1") (pinfunction "ODT_K1") (pintype "input"))
    )
    (net (code "74") (name "/DDR_ZQ1") (class "Default")
      (node (ref "R128") (pin "1") (pinfunction "1_1") (pintype "passive"))
      (node (ref "U14") (pin "L8") (pinfunction "ZQ_L8") (pintype "input"))
    )
    (net (code "75") (name "/DDR_ZQ2") (class "Default")
      (node (ref "R159") (pin "1") (pinfunction "1_1") (pintype "passive"))
      (node (ref "U15") (pin "L8") (pinfunction "ZQ_L8") (pintype "input"))
    )
    (net (code "76") (name "GND") (class "Default")
      (node (ref "C128") (pin "1") (pinfunction "1_1") (pintype "passive"))
      (node (ref "C129") (pin "1") (pinfunction "1_1") (pintype "passive"))
      (node (ref "C130") (pin "1") (pinfunction "1_1") (pintype "passive"))
      (node (ref "C131") (pin "1") (pinfunction "1_1") (pintype "passive"))
      (node (ref "C132") (pin "1") (pinfunction "1_1") (pintype "passive"))
      (node (ref "C133") (pin "1") (pinfunction "1_1") (pintype "passive"))
      (node (ref "C134") (pin "1") (pinfunction "1_1") (pintype "passive"))
      (node (ref "C135") (pin "1") (pinfunction "1_1") (pintype "passive"))
      (node (ref "C136") (pin "1") (pinfunction "1_1") (pintype "passive"))
      (node (ref "C137") (pin "1") (pinfunction "1_1") (pintype "passive"))
      (node (ref "C138") (pin "1") (pinfunction "1_1") (pintype "passive"))
      (node (ref "C139") (pin "1") (pinfunction "1_1") (pintype "passive"))
      (node (ref "C140") (pin "1") (pinfunction "1_1") (pintype "passive"))
      (node (ref "C141") (pin "1") (pinfunction "1_1") (pintype "passive"))
      (node (ref "C142") (pin "1") (pinfunction "1_1") (pintype "passive"))
      (node (ref "C143") (pin "1") (pinfunction "1_1") (pintype "passive"))
      (node (ref "C144") (pin "1") (pinfunction "1_1") (pintype "passive"))
      (node (ref "C145") (pin "1") (pinfunction "1_1") (pintype "passive"))
      (node (ref "C146") (pin "1") (pinfunction "1_1") (pintype "passive"))
      (node (ref "C147") (pin "1") (pinfunction "1_1") (pintype "passive"))
      (node (ref "C148") (pin "1") (pinfunction "1_1") (pintype "passive"))
      (node (ref "C150") (pin "1") (pinfunction "1_1") (pintype "passive"))
      (node (ref "C151") (pin "1") (pinfunction "1_1") (pintype "passive"))
      (node (ref "C152") (pin "1") (pinfunction "1_1") (pintype "passive"))
      (node (ref "C153") (pin "1") (pinfunction "1_1") (pintype "passive"))
      (node (ref "C154") (pin "1") (pinfunction "1_1") (pintype "passive"))
      (node (ref "C155") (pin "1") (pinfunction "1_1") (pintype "passive"))
      (node (ref "C156") (pin "1") (pinfunction "1_1") (pintype "passive"))
      (node (ref "C157") (pin "1") (pinfunction "1_1") (pintype "passive"))
      (node (ref "C158") (pin "1") (pinfunction "1_1") (pintype "passive"))
      (node (ref "C159") (pin "1") (pinfunction "1_1") (pintype "passive"))
      (node (ref "C160") (pin "1") (pinfunction "1_1") (pintype "passive"))
      (node (ref "C161") (pin "1") (pinfunction "1_1") (pintype "passive"))
      (node (ref "C162") (pin "1") (pinfunction "1_1") (pintype "passive"))
      (node (ref "C163") (pin "1") (pinfunction "1_1") (pintype "passive"))
      (node (ref "C164") (pin "1") (pinfunction "1_1") (pintype "passive"))
      (node (ref "C165") (pin "1") (pinfunction "1_1") (pintype "passive"))
      (node (ref "C166") (pin "1") (pinfunction "1_1") (pintype "passive"))
      (node (ref "C167") (pin "1") (pinfunction "1_1") (pintype "passive"))
      (node (ref "C168") (pin "1") (pinfunction "1_1") (pintype "passive"))
      (node (ref "C169") (pin "1") (pinfunction "1_1") (pintype "passive"))
      (node (ref "C170") (pin "1") (pinfunction "1_1") (pintype "passive"))
      (node (ref "R128") (pin "2") (pinfunction "2_2") (pintype "passive"))
      (node (ref "R159") (pin "2") (pinfunction "2_2") (pintype "passive"))
      (node (ref "U14") (pin "A9") (pinfunction "VSS_A9") (pintype "power_in"))
      (node (ref "U14") (pin "B1") (pinfunction "VSSQ_B1") (pintype "power_in"))
      (node (ref "U14") (pin "B3") (pinfunction "VSS_B3") (pintype "power_in"))
      (node (ref "U14") (pin "B9") (pinfunction "VSSQ_B9") (pintype "power_in"))
      (node (ref "U14") (pin "D1") (pinfunction "VSSQ_D1") (pintype "power_in"))
      (node (ref "U14") (pin "D8") (pinfunction "VSSQ_D8") (pintype "power_in"))
      (node (ref "U14") (pin "E1") (pinfunction "VSS_E1") (pintype "power_in"))
      (node (ref "U14") (pin "E2") (pinfunction "VSSQ_E2") (pintype "power_in"))
      (node (ref "U14") (pin "E8") (pinfunction "VSSQ_E8") (pintype "power_in"))
      (node (ref "U14") (pin "F9") (pinfunction "VSSQ_F9") (pintype "power_in"))
      (node (ref "U14") (pin "G1") (pinfunction "VSSQ_G1") (pintype "power_in"))
      (node (ref "U14") (pin "G8") (pinfunction "VSS_G8") (pintype "power_in"))
      (node (ref "U14") (pin "G9") (pinfunction "VSSQ_G9") (pintype "power_in"))
      (node (ref "U14") (pin "J2") (pinfunction "VSS_J2") (pintype "power_in"))
      (node (ref "U14") (pin "J8") (pinfunction "VSS_J8") (pintype "power_in"))
      (node (ref "U14") (pin "M1") (pinfunction "VSS_M1") (pintype "power_in"))
      (node (ref "U14") (pin "M9") (pinfunction "VSS_M9") (pintype "power_in"))
      (node (ref "U14") (pin "P1") (pinfunction "VSS_P1") (pintype "power_in"))
      (node (ref "U14") (pin "P9") (pinfunction "VSS_P9") (pintype "power_in"))
      (node (ref "U14") (pin "T1") (pinfunction "VSS_T1") (pintype "power_in"))
      (node (ref "U14") (pin "T9") (pinfunction "VSS_T9") (pintype "power_in"))
      (node (ref "U15") (pin "A9") (pinfunction "VSS_A9") (pintype "power_in"))
      (node (ref "U15") (pin "B1") (pinfunction "VSSQ_B1") (pintype "power_in"))
      (node (ref "U15") (pin "B3") (pinfunction "VSS_B3") (pintype "power_in"))
      (node (ref "U15") (pin "B9") (pinfunction "VSSQ_B9") (pintype "power_in"))
      (node (ref "U15") (pin "D1") (pinfunction "VSSQ_D1") (pintype "power_in"))
      (node (ref "U15") (pin "D8") (pinfunction "VSSQ_D8") (pintype "power_in"))
      (node (ref "U15") (pin "E1") (pinfunction "VSS_E1") (pintype "power_in"))
      (node (ref "U15") (pin "E2") (pinfunction "VSSQ_E2") (pintype "power_in"))
      (node (ref "U15") (pin "E8") (pinfunction "VSSQ_E8") (pintype "power_in"))
      (node (ref "U15") (pin "F9") (pinfunction "VSSQ_F9") (pintype "power_in"))
      (node (ref "U15") (pin "G1") (pinfunction "VSSQ_G1") (pintype "power_in"))
      (node (ref "U15") (pin "G8") (pinfunction "VSS_G8") (pintype "power_in"))
      (node (ref "U15") (pin "G9") (pinfunction "VSSQ_G9") (pintype "power_in"))
      (node (ref "U15") (pin "J2") (pinfunction "VSS_J2") (pintype "power_in"))
      (node (ref "U15") (pin "J8") (pinfunction "VSS_J8") (pintype "power_in"))
      (node (ref "U15") (pin "M1") (pinfunction "VSS_M1") (pintype "power_in"))
      (node (ref "U15") (pin "M9") (pinfunction "VSS_M9") (pintype "power_in"))
      (node (ref "U15") (pin "P1") (pinfunction "VSS_P1") (pintype "power_in"))
      (node (ref "U15") (pin "P9") (pinfunction "VSS_P9") (pintype "power_in"))
      (node (ref "U15") (pin "T1") (pinfunction "VSS_T1") (pintype "power_in"))
      (node (ref "U15") (pin "T9") (pinfunction "VSS_T9") (pintype "power_in"))
    )
    (net (code "77") (name "unconnected-(U14C-NC-PadJ1)") (class "Default")
      (node (ref "U14") (pin "J1") (pinfunction "NC_J1") (pintype "passive+no_connect"))
    )
    (net (code "78") (name "unconnected-(U14C-NC-PadJ9)") (class "Default")
      (node (ref "U14") (pin "J9") (pinfunction "NC_J9") (pintype "passive+no_connect"))
    )
    (net (code "79") (name "unconnected-(U14C-NC-PadL1)") (class "Default")
      (node (ref "U14") (pin "L1") (pinfunction "NC_L1") (pintype "passive+no_connect"))
    )
    (net (code "80") (name "unconnected-(U14C-NC-PadL9)") (class "Default")
      (node (ref "U14") (pin "L9") (pinfunction "NC_L9") (pintype "passive+no_connect"))
    )
    (net (code "81") (name "unconnected-(U14C-NC-PadM7)") (class "Default")
      (node (ref "U14") (pin "M7") (pinfunction "NC_M7") (pintype "passive+no_connect"))
    )
    (net (code "82") (name "unconnected-(U15C-NC-PadJ1)") (class "Default")
      (node (ref "U15") (pin "J1") (pinfunction "NC_J1") (pintype "passive+no_connect"))
    )
    (net (code "83") (name "unconnected-(U15C-NC-PadJ9)") (class "Default")
      (node (ref "U15") (pin "J9") (pinfunction "NC_J9") (pintype "passive+no_connect"))
    )
    (net (code "84") (name "unconnected-(U15C-NC-PadL1)") (class "Default")
      (node (ref "U15") (pin "L1") (pinfunction "NC_L1") (pintype "passive+no_connect"))
    )
    (net (code "85") (name "unconnected-(U15C-NC-PadL9)") (class "Default")
      (node (ref "U15") (pin "L9") (pinfunction "NC_L9") (pintype "passive+no_connect"))
    )
    (net (code "86") (name "unconnected-(U15C-NC-PadM7)") (class "Default")
      (node (ref "U15") (pin "M7") (pinfunction "NC_M7") (pintype "passive+no_connect"))
    )
  )
)
